# Sheet1.net
KiCad netlist of a schematic drawn in Altium Designer
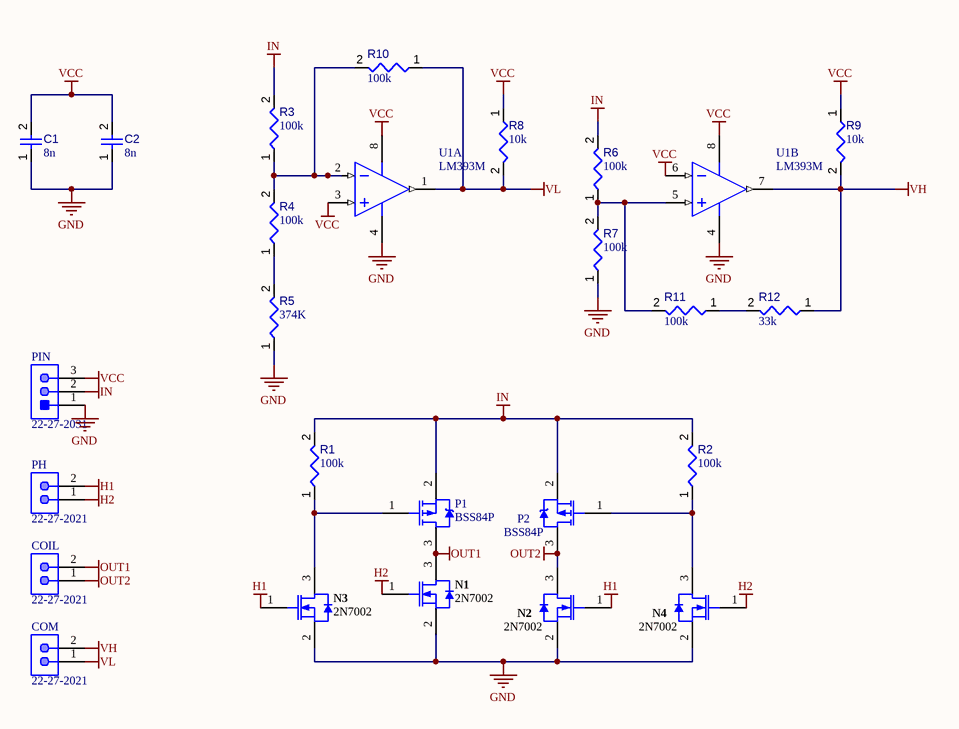
[diagram p0: Sheet1.SchDoc]

(export (version "E")
  (design (tool "Eeschema 10.0.6"))
  (components
    (comp (ref "C1")
      (value "8n")
      (footprint "CAPC2013X135X45NL10T25")
      (description "Chip Capacitor, 10 uF, +/- 10%, 16 V, 0805 (2012 Metric)")
      (fields (field (name "TOLERANCE") "10%") (field (name "Comment") "Capacitor 10 uF +/- 10% 16 V 0805"))
      (libsource (lib "Pontificia Universidad Javeriana") (part "CAP-NP-2"))
    )
    (comp (ref "C2")
      (value "8n")
      (footprint "CAPC2013X135X45NL10T25")
      (description "Chip Capacitor, 10 uF, +/- 10%, 16 V, 0805 (2012 Metric)")
      (fields (field (name "TOLERANCE") "10%") (field (name "Comment") "Capacitor 10 uF +/- 10% 16 V 0805"))
      (libsource (lib "Pontificia Universidad Javeriana") (part "CAP-NP-2"))
    )
    (comp (ref "COIL")
      (value "22-27-2021")
      (footprint "MOLX-22-27-2021_V")
      (fields (field (name "MANUFACTURER") "Molex") (field (name "PARTNUMBER") "0022272021"))
      (libsource (lib "Altium Content Vault") (part "CN-1P-M-R2"))
    )
    (comp (ref "COM")
      (value "22-27-2021")
      (footprint "MOLX-22-27-2021_V")
      (fields (field (name "MANUFACTURER") "Molex") (field (name "PARTNUMBER") "0022272021"))
      (libsource (lib "Altium Content Vault") (part "CN-1P-M-R2"))
    )
    (comp (ref "N1")
      (value "2N7002")
      (footprint "INF-PG-SOT23_M")
      (fields (field (name "MANUFACTURER") "Infineon"))
      (libsource (lib "Altium Content Vault") (part "INF-NDMOS-GSD-3"))
    )
    (comp (ref "N2")
      (value "2N7002")
      (footprint "INF-PG-SOT23_M")
      (fields (field (name "MANUFACTURER") "Infineon"))
      (libsource (lib "Altium Content Vault") (part "INF-NDMOS-GSD-3"))
    )
    (comp (ref "N3")
      (value "2N7002")
      (footprint "INF-PG-SOT23_M")
      (fields (field (name "MANUFACTURER") "Infineon"))
      (libsource (lib "Altium Content Vault") (part "INF-NDMOS-GSD-3"))
    )
    (comp (ref "N4")
      (value "2N7002")
      (footprint "INF-PG-SOT23_M")
      (fields (field (name "MANUFACTURER") "Infineon"))
      (libsource (lib "Altium Content Vault") (part "INF-NDMOS-GSD-3"))
    )
    (comp (ref "P1")
      (value "BSS84P")
      (footprint "INF-PG-SOT23_N")
      (fields (field (name "MANUFACTURER") "Infineon"))
      (libsource (lib "Altium Content Vault") (part "INF-PEMOS-GSD-3-B"))
    )
    (comp (ref "P2")
      (value "BSS84P")
      (footprint "INF-PG-SOT23_N")
      (fields (field (name "MANUFACTURER") "Infineon"))
      (libsource (lib "Altium Content Vault") (part "INF-PEMOS-GSD-3-B"))
    )
    (comp (ref "PH")
      (value "22-27-2021")
      (footprint "MOLX-22-27-2021_V")
      (fields (field (name "MANUFACTURER") "Molex") (field (name "PARTNUMBER") "0022272021"))
      (libsource (lib "Altium Content Vault") (part "CN-1P-M-R2"))
    )
    (comp (ref "PIN")
      (value "22-27-2031")
      (footprint "MOLX-22-27-2031_V")
      (fields (field (name "MANUFACTURER") "Molex"))
      (libsource (lib "Altium Content Vault") (part "CN-1P-M-R3"))
    )
    (comp (ref "R1")
      (value "100k")
      (footprint "RESC3216X60X45ML15T20")
      (description "Chip Resistor, 100 KOhm, +/- 1%, 0.25 W, -55 to 155 degC, 1206 (3216 Metric)")
      (fields (field (name "TOLERANCE") "1%") (field (name "POWER") "250mW"))
      (libsource (lib "Pontificia Universidad Javeriana") (part "RES-2"))
    )
    (comp (ref "R2")
      (value "100k")
      (footprint "RESC3216X60X45ML15T20")
      (description "Chip Resistor, 100 KOhm, +/- 1%, 0.25 W, -55 to 155 degC, 1206 (3216 Metric)")
      (fields (field (name "TOLERANCE") "1%") (field (name "POWER") "250mW"))
      (libsource (lib "Pontificia Universidad Javeriana") (part "RES-2"))
    )
    (comp (ref "R3")
      (value "100k")
      (footprint "RESC3216X60X45ML15T20")
      (description "Chip Resistor, 100 KOhm, +/- 1%, 0.25 W, -55 to 155 degC, 1206 (3216 Metric)")
      (fields (field (name "TOLERANCE") "1%") (field (name "POWER") "250mW"))
      (libsource (lib "Pontificia Universidad Javeriana") (part "RES-2"))
    )
    (comp (ref "R4")
      (value "100k")
      (footprint "RESC3216X60X45ML15T20")
      (description "Chip Resistor, 100 KOhm, +/- 1%, 0.25 W, -55 to 155 degC, 1206 (3216 Metric)")
      (fields (field (name "TOLERANCE") "1%") (field (name "POWER") "250mW"))
      (libsource (lib "Pontificia Universidad Javeriana") (part "RES-2"))
    )
    (comp (ref "R5")
      (value "374K")
      (footprint "RESC3216X60X45ML15T20")
      (description "Chip Resistor, 100 KOhm, +/- 1%, 0.25 W, -55 to 155 degC, 1206 (3216 Metric)")
      (fields (field (name "TOLERANCE") "1%") (field (name "POWER") "250mW"))
      (libsource (lib "Pontificia Universidad Javeriana") (part "RES-2"))
    )
    (comp (ref "R6")
      (value "100k")
      (footprint "RESC3216X60X45ML15T20")
      (description "Chip Resistor, 100 KOhm, +/- 1%, 0.25 W, -55 to 155 degC, 1206 (3216 Metric)")
      (fields (field (name "TOLERANCE") "1%") (field (name "POWER") "250mW"))
      (libsource (lib "Pontificia Universidad Javeriana") (part "RES-2"))
    )
    (comp (ref "R7")
      (value "100k")
      (footprint "RESC3216X60X45ML15T20")
      (description "Chip Resistor, 100 KOhm, +/- 1%, 0.25 W, -55 to 155 degC, 1206 (3216 Metric)")
      (fields (field (name "TOLERANCE") "1%") (field (name "POWER") "250mW"))
      (libsource (lib "Pontificia Universidad Javeriana") (part "RES-2"))
    )
    (comp (ref "R8")
      (value "10k")
      (footprint "RESC2013X50X35ML15T15")
      (description "Chip Resistor, 10 KOhm, +/- 1%, 125 mW, -55 to 155 degC, 0805 (2012 Metric)")
      (fields (field (name "TOLERANCE") "1%") (field (name "POWER") "125mW"))
      (libsource (lib "Pontificia Universidad Javeriana") (part "RES-2"))
    )
    (comp (ref "R9")
      (value "10k")
      (footprint "RESC2013X50X35ML15T15")
      (description "Chip Resistor, 10 KOhm, +/- 1%, 125 mW, -55 to 155 degC, 0805 (2012 Metric)")
      (fields (field (name "TOLERANCE") "1%") (field (name "POWER") "125mW"))
      (libsource (lib "Pontificia Universidad Javeriana") (part "RES-2"))
    )
    (comp (ref "R10")
      (value "100k")
      (footprint "RESC3216X60X45ML15T20")
      (description "Chip Resistor, 100 KOhm, +/- 1%, 0.25 W, -55 to 155 degC, 1206 (3216 Metric)")
      (fields (field (name "TOLERANCE") "1%") (field (name "POWER") "250mW"))
      (libsource (lib "Pontificia Universidad Javeriana") (part "RES-2"))
    )
    (comp (ref "R11")
      (value "100k")
      (footprint "RESC3216X60X45ML15T20")
      (description "Chip Resistor, 100 KOhm, +/- 1%, 0.25 W, -55 to 155 degC, 1206 (3216 Metric)")
      (fields (field (name "TOLERANCE") "1%") (field (name "POWER") "250mW"))
      (libsource (lib "Pontificia Universidad Javeriana") (part "RES-2"))
    )
    (comp (ref "R12")
      (value "33k")
      (footprint "RESC3216X60X45ML15T20")
      (description "Chip Resistor, 100 KOhm, +/- 1%, 0.25 W, -55 to 155 degC, 1206 (3216 Metric)")
      (fields (field (name "TOLERANCE") "1%") (field (name "POWER") "250mW"))
      (libsource (lib "Pontificia Universidad Javeriana") (part "RES-2"))
    )
    (comp (ref "U1")
      (value "LM393M")
      (footprint "D0008A_L")
      (description "Low Power Low Offset Voltage Dual Comparator, 8-pin Narrow SOIC")
      (fields (field (name "MANUFACTURER") "Texas Instruments"))
      (libsource (lib "Altium Content Vault") (part "AN-COMP-LM193-8"))
    )
  )
  (nets
    (net (code "1") (name "GND") (class "Default")
      (node (ref "C1") (pin "1") (pinfunction "1_1") (pintype "passive"))
      (node (ref "C2") (pin "1") (pinfunction "1_1") (pintype "passive"))
      (node (ref "N1") (pin "2") (pinfunction "SOURCE_2") (pintype "passive"))
      (node (ref "N2") (pin "2") (pinfunction "SOURCE_2") (pintype "passive"))
      (node (ref "N3") (pin "2") (pinfunction "SOURCE_2") (pintype "passive"))
      (node (ref "N4") (pin "2") (pinfunction "SOURCE_2") (pintype "passive"))
      (node (ref "PIN") (pin "1") (pinfunction "1_1") (pintype "passive"))
      (node (ref "R5") (pin "1") (pinfunction "1_1") (pintype "passive"))
      (node (ref "R7") (pin "1") (pinfunction "1_1") (pintype "passive"))
      (node (ref "U1") (pin "4") (pinfunction "GND_4") (pintype "power_in"))
    )
    (net (code "2") (name "H1") (class "Default")
      (node (ref "N2") (pin "1") (pinfunction "GATE_1") (pintype "passive"))
      (node (ref "N3") (pin "1") (pinfunction "GATE_1") (pintype "passive"))
      (node (ref "PH") (pin "2") (pinfunction "2_2") (pintype "passive"))
    )
    (net (code "3") (name "H2") (class "Default")
      (node (ref "N1") (pin "1") (pinfunction "GATE_1") (pintype "passive"))
      (node (ref "N4") (pin "1") (pinfunction "GATE_1") (pintype "passive"))
      (node (ref "PH") (pin "1") (pinfunction "1_1") (pintype "passive"))
    )
    (net (code "4") (name "IN") (class "Default")
      (node (ref "P1") (pin "2") (pinfunction "SOURCE_2") (pintype "passive"))
      (node (ref "P2") (pin "2") (pinfunction "SOURCE_2") (pintype "passive"))
      (node (ref "PIN") (pin "2") (pinfunction "2_2") (pintype "passive"))
      (node (ref "R1") (pin "2") (pinfunction "2_2") (pintype "passive"))
      (node (ref "R2") (pin "2") (pinfunction "2_2") (pintype "passive"))
      (node (ref "R3") (pin "2") (pinfunction "2_2") (pintype "passive"))
      (node (ref "R6") (pin "2") (pinfunction "2_2") (pintype "passive"))
    )
    (net (code "5") (name "Net-(N3-DRAIN)") (class "Default")
      (node (ref "N3") (pin "3") (pinfunction "DRAIN_3") (pintype "passive"))
      (node (ref "P1") (pin "1") (pinfunction "GATE_1") (pintype "passive"))
      (node (ref "R1") (pin "1") (pinfunction "1_1") (pintype "passive"))
    )
    (net (code "6") (name "Net-(N4-DRAIN)") (class "Default")
      (node (ref "N4") (pin "3") (pinfunction "DRAIN_3") (pintype "passive"))
      (node (ref "P2") (pin "1") (pinfunction "GATE_1") (pintype "passive"))
      (node (ref "R2") (pin "1") (pinfunction "1_1") (pintype "passive"))
    )
    (net (code "7") (name "Net-(R4-Pad1)") (class "Default")
      (node (ref "R4") (pin "1") (pinfunction "1_1") (pintype "passive"))
      (node (ref "R5") (pin "2") (pinfunction "2_2") (pintype "passive"))
    )
    (net (code "8") (name "Net-(R11-Pad1)") (class "Default")
      (node (ref "R11") (pin "1") (pinfunction "1_1") (pintype "passive"))
      (node (ref "R12") (pin "2") (pinfunction "2_2") (pintype "passive"))
    )
    (net (code "9") (name "Net-(U1A-INA-)") (class "Default")
      (node (ref "R10") (pin "2") (pinfunction "2_2") (pintype "passive"))
      (node (ref "R3") (pin "1") (pinfunction "1_1") (pintype "passive"))
      (node (ref "R4") (pin "2") (pinfunction "2_2") (pintype "passive"))
      (node (ref "U1") (pin "2") (pinfunction "INA-_2") (pintype "input"))
    )
    (net (code "10") (name "Net-(U1B-INB+)") (class "Default")
      (node (ref "R11") (pin "2") (pinfunction "2_2") (pintype "passive"))
      (node (ref "R6") (pin "1") (pinfunction "1_1") (pintype "passive"))
      (node (ref "R7") (pin "2") (pinfunction "2_2") (pintype "passive"))
      (node (ref "U1") (pin "5") (pinfunction "INB+_5") (pintype "input"))
    )
    (net (code "11") (name "OUT1") (class "Default")
      (node (ref "COIL") (pin "2") (pinfunction "2_2") (pintype "passive"))
      (node (ref "N1") (pin "3") (pinfunction "DRAIN_3") (pintype "passive"))
      (node (ref "P1") (pin "3") (pinfunction "DRAIN_3") (pintype "passive"))
    )
    (net (code "12") (name "OUT2") (class "Default")
      (node (ref "COIL") (pin "1") (pinfunction "1_1") (pintype "passive"))
      (node (ref "N2") (pin "3") (pinfunction "DRAIN_3") (pintype "passive"))
      (node (ref "P2") (pin "3") (pinfunction "DRAIN_3") (pintype "passive"))
    )
    (net (code "13") (name "VCC") (class "Default")
      (node (ref "C1") (pin "2") (pinfunction "2_2") (pintype "passive"))
      (node (ref "C2") (pin "2") (pinfunction "2_2") (pintype "passive"))
      (node (ref "PIN") (pin "3") (pinfunction "3_3") (pintype "passive"))
      (node (ref "R8") (pin "1") (pinfunction "1_1") (pintype "passive"))
      (node (ref "R9") (pin "1") (pinfunction "1_1") (pintype "passive"))
      (node (ref "U1") (pin "3") (pinfunction "INA+_3") (pintype "input"))
      (node (ref "U1") (pin "6") (pinfunction "INB-_6") (pintype "input"))
      (node (ref "U1") (pin "8") (pinfunction "V+_8") (pintype "power_in"))
    )
    (net (code "14") (name "VH") (class "Default")
      (node (ref "COM") (pin "2") (pinfunction "2_2") (pintype "passive"))
      (node (ref "R12") (pin "1") (pinfunction "1_1") (pintype "passive"))
      (node (ref "R9") (pin "2") (pinfunction "2_2") (pintype "passive"))
      (node (ref "U1") (pin "7") (pinfunction "OUTB_7") (pintype "output"))
    )
    (net (code "15") (name "VL") (class "Default")
      (node (ref "COM") (pin "1") (pinfunction "1_1") (pintype "passive"))
      (node (ref "R10") (pin "1") (pinfunction "1_1") (pintype "passive"))
      (node (ref "R8") (pin "2") (pinfunction "2_2") (pintype "passive"))
      (node (ref "U1") (pin "1") (pinfunction "OUTA_1") (pintype "output"))
    )
  )
)
